# homeboard2.net
KiCad netlist of a schematic drawn in EAGLE
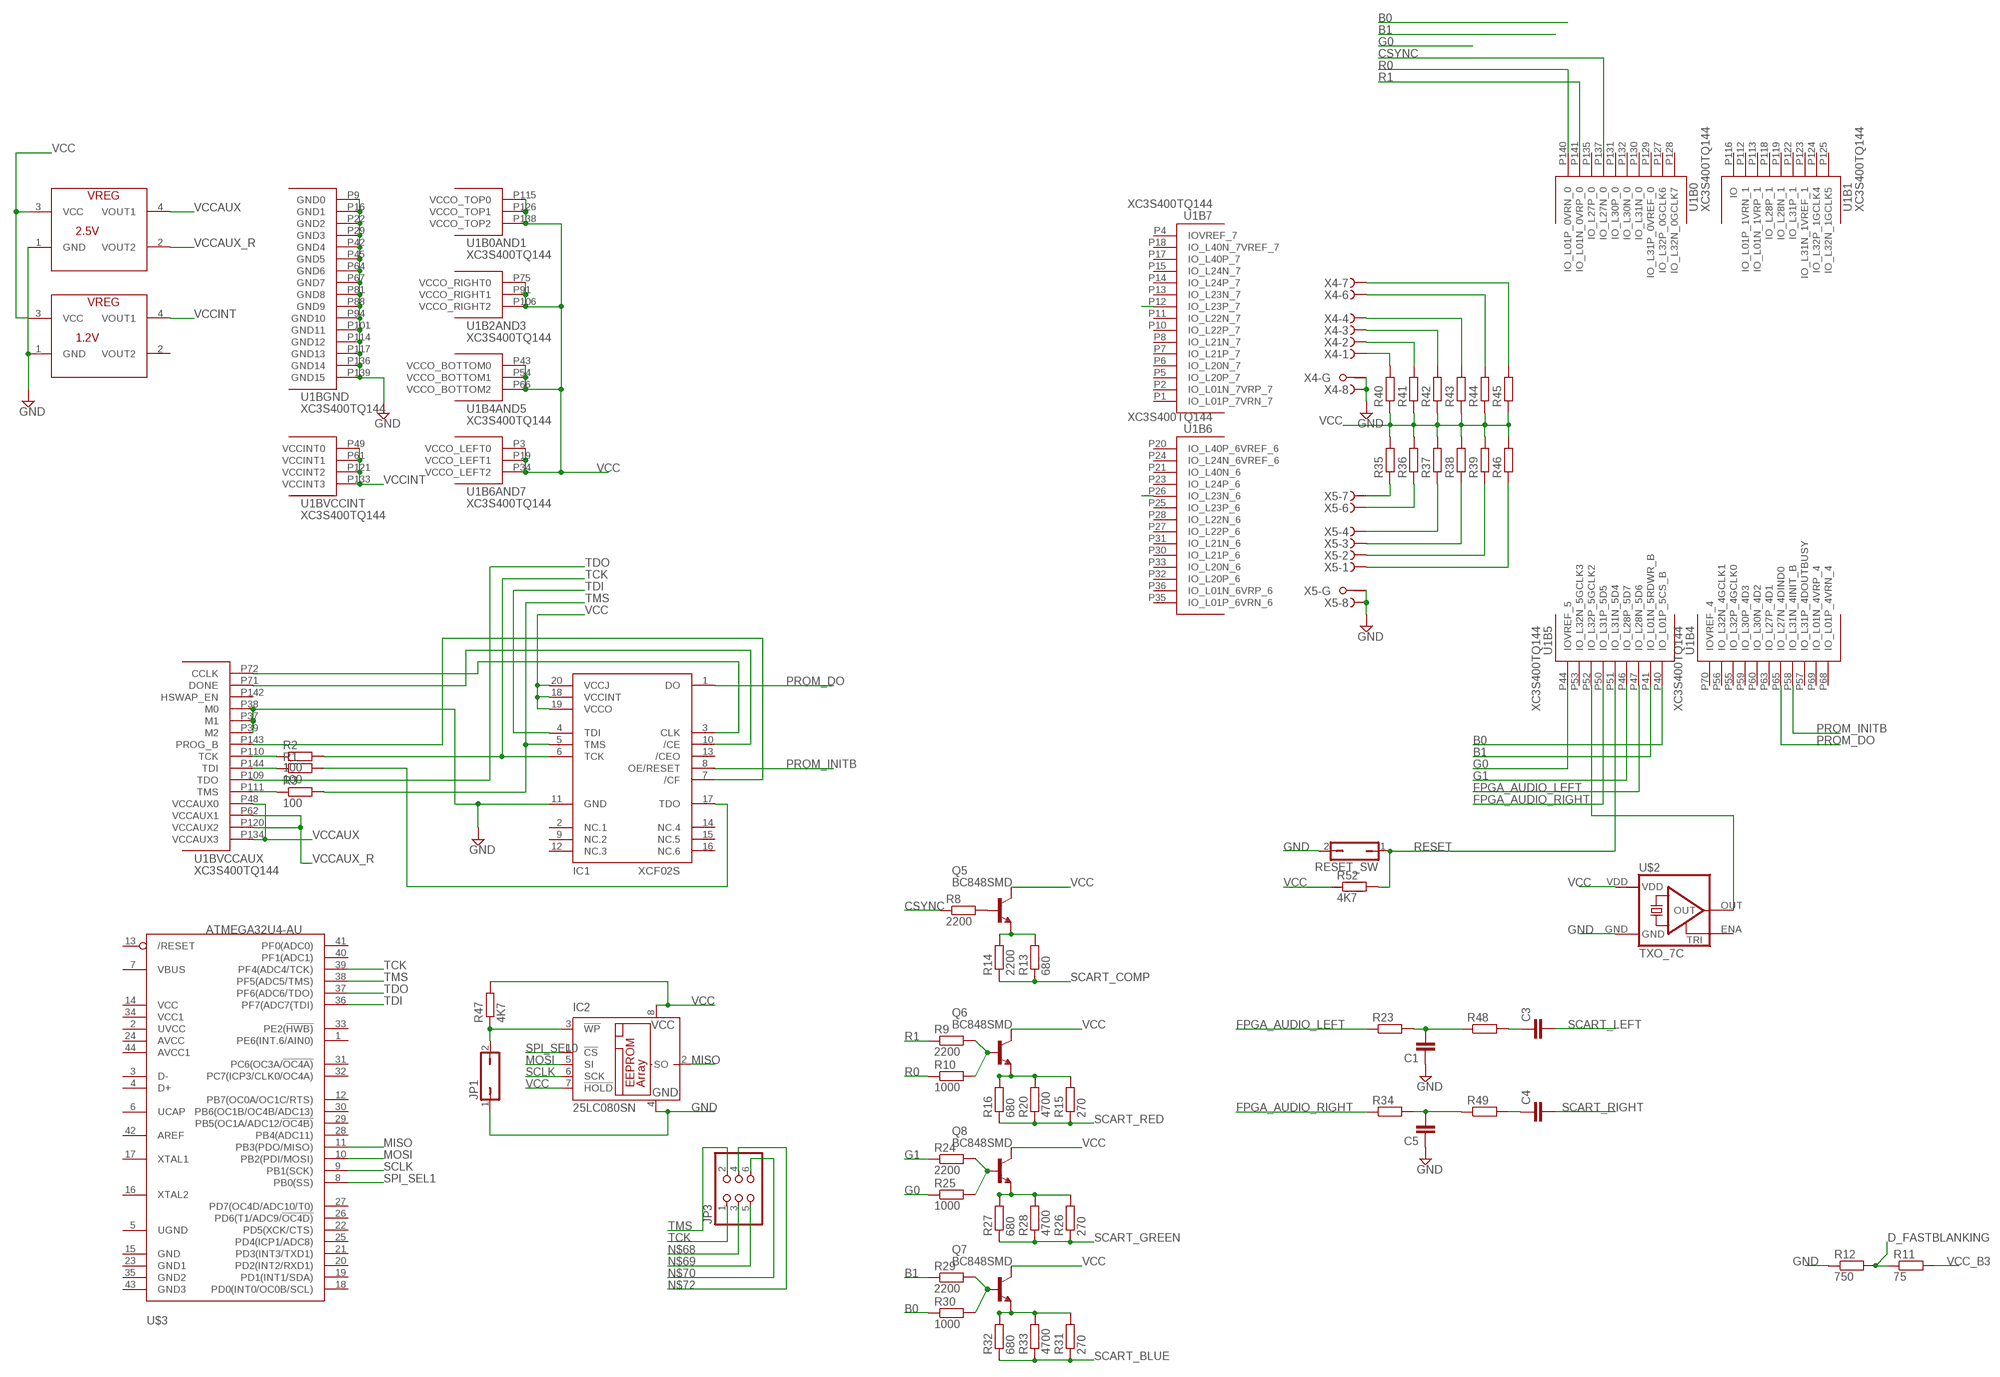
[diagram p0: schematic, sheet 1, part 1 of 3]
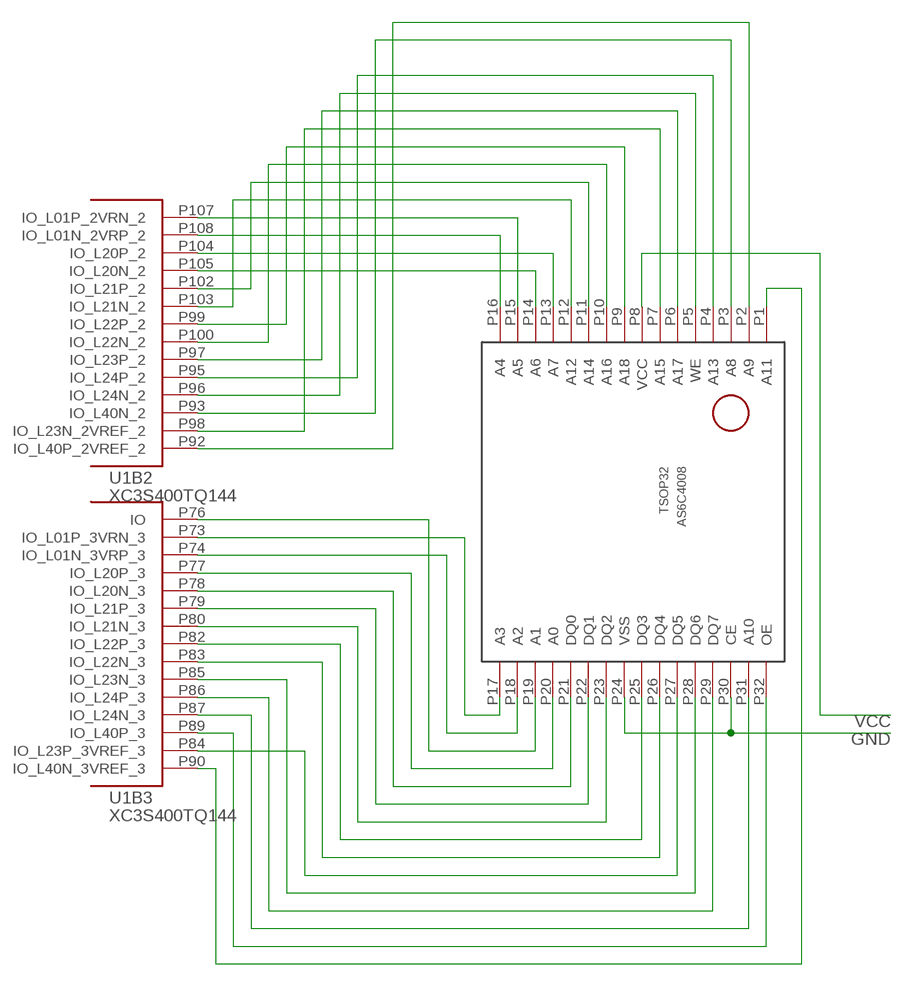
[diagram p1: schematic, sheet 1, part 2 of 3]
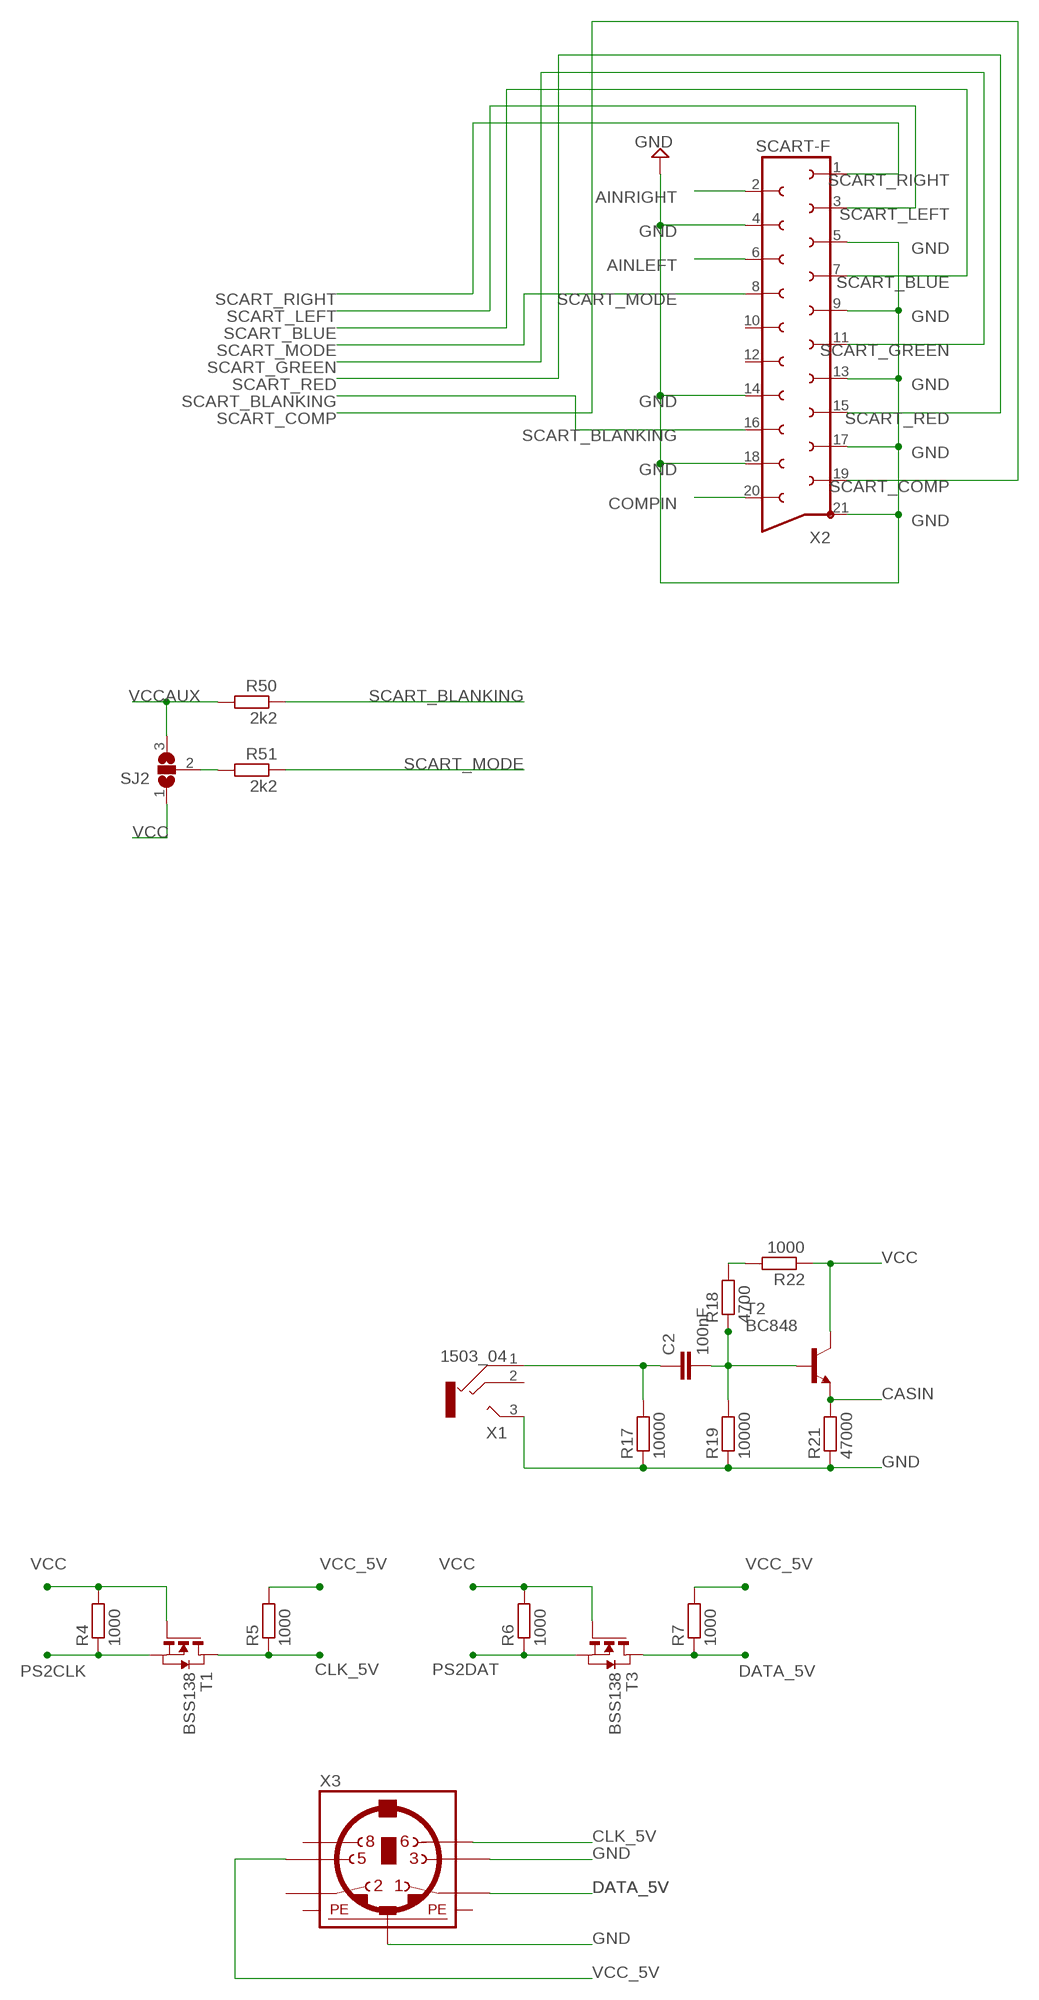
[diagram p2: schematic, sheet 1, part 3 of 3]

(export (version "E")
  (design (tool "Eeschema 10.0.6"))
  (components
    (comp (ref "C1")
      (value "C-EUC0603")
      (footprint "eagle-import:C0603")
      (libsource (lib "eagle-import") (part "C-EUC0603"))
    )
    (comp (ref "C2")
      (value "100nF")
      (footprint "eagle-import:C0603")
      (libsource (lib "eagle-import") (part "C-EUC0603"))
    )
    (comp (ref "C3")
      (value "C-EUC0603")
      (footprint "eagle-import:C0603")
      (libsource (lib "eagle-import") (part "C-EUC0603"))
    )
    (comp (ref "C4")
      (value "C-EUC0603")
      (footprint "eagle-import:C0603")
      (libsource (lib "eagle-import") (part "C-EUC0603"))
    )
    (comp (ref "C5")
      (value "C-EUC0603")
      (footprint "eagle-import:C0603")
      (libsource (lib "eagle-import") (part "C-EUC0603"))
    )
    (comp (ref "IC1")
      (value "XCF02S")
      (footprint "eagle-import:VO20")
      (libsource (lib "eagle-import") (part "XCF02S"))
    )
    (comp (ref "IC2")
      (value "25LC080SN")
      (footprint "eagle-import:SO-08")
      (fields (field (name "MF") "MICROCHIP") (field (name "MPN") "25LC080/SN"))
      (libsource (lib "eagle-import") (part "25SNLC080"))
    )
    (comp (ref "JP1")
      (value "JP1Q")
      (footprint "eagle-import:JP1")
      (libsource (lib "eagle-import") (part "JP1Q"))
    )
    (comp (ref "JP3")
      (value "PINHD-2X3")
      (footprint "eagle-import:2X03")
      (libsource (lib "eagle-import") (part "PINHD-2X3"))
    )
    (comp (ref "Q5")
      (value "BC848SMD")
      (footprint "eagle-import:SOT23")
      (libsource (lib "eagle-import") (part "BC848SMD"))
    )
    (comp (ref "Q6")
      (value "BC848SMD")
      (footprint "eagle-import:SOT23")
      (libsource (lib "eagle-import") (part "BC848SMD"))
    )
    (comp (ref "Q7")
      (value "BC848SMD")
      (footprint "eagle-import:SOT23")
      (libsource (lib "eagle-import") (part "BC848SMD"))
    )
    (comp (ref "Q8")
      (value "BC848SMD")
      (footprint "eagle-import:SOT23")
      (libsource (lib "eagle-import") (part "BC848SMD"))
    )
    (comp (ref "R1")
      (value "100")
      (footprint "eagle-import:R0805")
      (libsource (lib "eagle-import") (part "R-EU_R0805"))
    )
    (comp (ref "R2")
      (value "100")
      (footprint "eagle-import:R0805")
      (libsource (lib "eagle-import") (part "R-EU_R0805"))
    )
    (comp (ref "R3")
      (value "100")
      (footprint "eagle-import:R0805")
      (libsource (lib "eagle-import") (part "R-EU_R0805"))
    )
    (comp (ref "R4")
      (value "1000")
      (footprint "eagle-import:R0805")
      (libsource (lib "eagle-import") (part "R-EU_R0805"))
    )
    (comp (ref "R5")
      (value "1000")
      (footprint "eagle-import:R0805")
      (libsource (lib "eagle-import") (part "R-EU_R0805"))
    )
    (comp (ref "R6")
      (value "1000")
      (footprint "eagle-import:R0805")
      (libsource (lib "eagle-import") (part "R-EU_R0805"))
    )
    (comp (ref "R7")
      (value "1000")
      (footprint "eagle-import:R0805")
      (libsource (lib "eagle-import") (part "R-EU_R0805"))
    )
    (comp (ref "R8")
      (value "2200")
      (footprint "eagle-import:R0805")
      (libsource (lib "eagle-import") (part "R-EU_R0805"))
    )
    (comp (ref "R9")
      (value "2200")
      (footprint "eagle-import:R0805")
      (libsource (lib "eagle-import") (part "R-EU_R0805"))
    )
    (comp (ref "R10")
      (value "1000")
      (footprint "eagle-import:R0805")
      (libsource (lib "eagle-import") (part "R-EU_R0805"))
    )
    (comp (ref "R11")
      (value "75")
      (footprint "eagle-import:R0805")
      (libsource (lib "eagle-import") (part "R-EU_R0805"))
    )
    (comp (ref "R12")
      (value "750")
      (footprint "eagle-import:R0805")
      (libsource (lib "eagle-import") (part "R-EU_R0805"))
    )
    (comp (ref "R13")
      (value "680")
      (footprint "eagle-import:R0805")
      (libsource (lib "eagle-import") (part "R-EU_R0805"))
    )
    (comp (ref "R14")
      (value "2200")
      (footprint "eagle-import:R0805")
      (libsource (lib "eagle-import") (part "R-EU_R0805"))
    )
    (comp (ref "R15")
      (value "270")
      (footprint "eagle-import:R0805")
      (libsource (lib "eagle-import") (part "R-EU_R0805"))
    )
    (comp (ref "R16")
      (value "680")
      (footprint "eagle-import:R0805")
      (libsource (lib "eagle-import") (part "R-EU_R0805"))
    )
    (comp (ref "R17")
      (value "10000")
      (footprint "eagle-import:R0805")
      (libsource (lib "eagle-import") (part "R-EU_R0805"))
    )
    (comp (ref "R18")
      (value "4700")
      (footprint "eagle-import:R0805")
      (libsource (lib "eagle-import") (part "R-EU_R0805"))
    )
    (comp (ref "R19")
      (value "10000")
      (footprint "eagle-import:R0805")
      (libsource (lib "eagle-import") (part "R-EU_R0805"))
    )
    (comp (ref "R20")
      (value "4700")
      (footprint "eagle-import:R0805")
      (libsource (lib "eagle-import") (part "R-EU_R0805"))
    )
    (comp (ref "R21")
      (value "47000")
      (footprint "eagle-import:R0805")
      (libsource (lib "eagle-import") (part "R-EU_R0805"))
    )
    (comp (ref "R22")
      (value "1000")
      (footprint "eagle-import:R0805")
      (libsource (lib "eagle-import") (part "R-EU_R0805"))
    )
    (comp (ref "R23")
      (value "R-EU_M0805")
      (footprint "eagle-import:M0805")
      (libsource (lib "eagle-import") (part "resistor_R-EU_M0805"))
    )
    (comp (ref "R24")
      (value "2200")
      (footprint "eagle-import:R0805")
      (libsource (lib "eagle-import") (part "R-EU_R0805"))
    )
    (comp (ref "R25")
      (value "1000")
      (footprint "eagle-import:R0805")
      (libsource (lib "eagle-import") (part "R-EU_R0805"))
    )
    (comp (ref "R26")
      (value "270")
      (footprint "eagle-import:R0805")
      (libsource (lib "eagle-import") (part "R-EU_R0805"))
    )
    (comp (ref "R27")
      (value "680")
      (footprint "eagle-import:R0805")
      (libsource (lib "eagle-import") (part "R-EU_R0805"))
    )
    (comp (ref "R28")
      (value "4700")
      (footprint "eagle-import:R0805")
      (libsource (lib "eagle-import") (part "R-EU_R0805"))
    )
    (comp (ref "R29")
      (value "2200")
      (footprint "eagle-import:R0805")
      (libsource (lib "eagle-import") (part "R-EU_R0805"))
    )
    (comp (ref "R30")
      (value "1000")
      (footprint "eagle-import:R0805")
      (libsource (lib "eagle-import") (part "R-EU_R0805"))
    )
    (comp (ref "R31")
      (value "270")
      (footprint "eagle-import:R0805")
      (libsource (lib "eagle-import") (part "R-EU_R0805"))
    )
    (comp (ref "R32")
      (value "680")
      (footprint "eagle-import:R0805")
      (libsource (lib "eagle-import") (part "R-EU_R0805"))
    )
    (comp (ref "R33")
      (value "4700")
      (footprint "eagle-import:R0805")
      (libsource (lib "eagle-import") (part "R-EU_R0805"))
    )
    (comp (ref "R34")
      (value "R-EU_M0805")
      (footprint "eagle-import:M0805")
      (libsource (lib "eagle-import") (part "resistor_R-EU_M0805"))
    )
    (comp (ref "R35")
      (value "R-EU_M0805")
      (footprint "eagle-import:M0805")
      (libsource (lib "eagle-import") (part "resistor_R-EU_M0805"))
    )
    (comp (ref "R36")
      (value "R-EU_M0805")
      (footprint "eagle-import:M0805")
      (libsource (lib "eagle-import") (part "resistor_R-EU_M0805"))
    )
    (comp (ref "R37")
      (value "R-EU_M0805")
      (footprint "eagle-import:M0805")
      (libsource (lib "eagle-import") (part "resistor_R-EU_M0805"))
    )
    (comp (ref "R38")
      (value "R-EU_M0805")
      (footprint "eagle-import:M0805")
      (libsource (lib "eagle-import") (part "resistor_R-EU_M0805"))
    )
    (comp (ref "R39")
      (value "R-EU_M0805")
      (footprint "eagle-import:M0805")
      (libsource (lib "eagle-import") (part "resistor_R-EU_M0805"))
    )
    (comp (ref "R40")
      (value "R-EU_M0805")
      (footprint "eagle-import:M0805")
      (libsource (lib "eagle-import") (part "resistor_R-EU_M0805"))
    )
    (comp (ref "R41")
      (value "R-EU_M0805")
      (footprint "eagle-import:M0805")
      (libsource (lib "eagle-import") (part "resistor_R-EU_M0805"))
    )
    (comp (ref "R42")
      (value "R-EU_M0805")
      (footprint "eagle-import:M0805")
      (libsource (lib "eagle-import") (part "resistor_R-EU_M0805"))
    )
    (comp (ref "R43")
      (value "R-EU_M0805")
      (footprint "eagle-import:M0805")
      (libsource (lib "eagle-import") (part "resistor_R-EU_M0805"))
    )
    (comp (ref "R44")
      (value "R-EU_M0805")
      (footprint "eagle-import:M0805")
      (libsource (lib "eagle-import") (part "resistor_R-EU_M0805"))
    )
    (comp (ref "R45")
      (value "R-EU_M0805")
      (footprint "eagle-import:M0805")
      (libsource (lib "eagle-import") (part "resistor_R-EU_M0805"))
    )
    (comp (ref "R46")
      (value "R-EU_M0805")
      (footprint "eagle-import:M0805")
      (libsource (lib "eagle-import") (part "resistor_R-EU_M0805"))
    )
    (comp (ref "R47")
      (value "4K7")
      (footprint "eagle-import:R0805")
      (libsource (lib "eagle-import") (part "R-EU_R0805"))
    )
    (comp (ref "R48")
      (value "R-EU_M0805")
      (footprint "eagle-import:M0805")
      (libsource (lib "eagle-import") (part "resistor_R-EU_M0805"))
    )
    (comp (ref "R49")
      (value "R-EU_M0805")
      (footprint "eagle-import:M0805")
      (libsource (lib "eagle-import") (part "resistor_R-EU_M0805"))
    )
    (comp (ref "R50")
      (value "2k2")
      (footprint "eagle-import:M0805")
      (libsource (lib "eagle-import") (part "resistor_R-EU_M0805"))
    )
    (comp (ref "R51")
      (value "2k2")
      (footprint "eagle-import:M0805")
      (libsource (lib "eagle-import") (part "resistor_R-EU_M0805"))
    )
    (comp (ref "R52")
      (value "4K7")
      (footprint "eagle-import:M0805")
      (libsource (lib "eagle-import") (part "resistor_R-EU_M0805"))
    )
    (comp (ref "REG1.2")
      (value "1.2V")
      (footprint "eagle-import:SOT223")
      (libsource (lib "eagle-import") (part "NX1117"))
    )
    (comp (ref "REG2.5")
      (value "2.5V")
      (footprint "eagle-import:SOT223")
      (libsource (lib "eagle-import") (part "NX1117"))
    )
    (comp (ref "RESET_SW")
      (value "JP1Q")
      (footprint "eagle-import:JP1")
      (libsource (lib "eagle-import") (part "JP1Q"))
    )
    (comp (ref "SJ2")
      (value "SJ2W")
      (footprint "eagle-import:SJ_2")
      (libsource (lib "eagle-import") (part "SJ2W"))
    )
    (comp (ref "T1")
      (value "BSS138")
      (footprint "eagle-import:SOT-23")
      (libsource (lib "eagle-import") (part "NMOSSOT23"))
    )
    (comp (ref "T2")
      (value "BC848")
      (footprint "eagle-import:SOT23")
      (libsource (lib "eagle-import") (part "BC848"))
    )
    (comp (ref "T3")
      (value "BSS138")
      (footprint "eagle-import:SOT-23")
      (libsource (lib "eagle-import") (part "NMOSSOT23"))
    )
    (comp (ref "U$1")
      (value "AS6C4008")
      (footprint "eagle-import:TSOP32")
      (libsource (lib "eagle-import") (part "AS6C4008"))
    )
    (comp (ref "U$2")
      (value "TXO_7C")
      (footprint "eagle-import:OSC_7C")
      (libsource (lib "eagle-import") (part "TXO_7C"))
    )
    (comp (ref "U$3")
      (value "ATMEGA32U4-AU")
      (footprint "eagle-import:TQFP44")
      (libsource (lib "eagle-import") (part "ATMEGA32U4-AU"))
    )
    (comp (ref "U1")
      (value "XC3S400TQ144")
      (footprint "eagle-import:TQ144")
      (libsource (lib "eagle-import") (part "XC3S400TQ144"))
    )
    (comp (ref "X1")
      (value "1503_04")
      (footprint "eagle-import:1503_04")
      (libsource (lib "eagle-import") (part "1503_04"))
    )
    (comp (ref "X2")
      (value "SCART-F")
      (footprint "eagle-import:SCART-F")
      (libsource (lib "eagle-import") (part "SCART-F"))
    )
    (comp (ref "X3")
      (value "MINI_DIN_6")
      (footprint "eagle-import:M_DIN6")
      (libsource (lib "eagle-import") (part "MINI_DIN_6"))
    )
    (comp (ref "X4")
      (value "F09HPS")
      (footprint "eagle-import:F09HP")
      (libsource (lib "eagle-import") (part "F09HPS"))
    )
    (comp (ref "X5")
      (value "F09HPS")
      (footprint "eagle-import:F09HP")
      (libsource (lib "eagle-import") (part "F09HPS"))
    )
  )
  (nets
    (net (code "1") (name "/AINLEFT") (class "Default")
      (node (ref "X2") (pin "6") (pinfunction "6_6") (pintype "passive"))
    )
    (net (code "2") (name "/AINRIGHT") (class "Default")
      (node (ref "X2") (pin "2") (pinfunction "2_2") (pintype "passive"))
    )
    (net (code "3") (name "/B0") (class "Default")
      (node (ref "R30") (pin "1") (pinfunction "1_1") (pintype "passive"))
      (node (ref "U1") (pin "P40") (pinfunction "IO_L01P_5CS_B_P40") (pintype "bidirectional"))
    )
    (net (code "4") (name "/B1") (class "Default")
      (node (ref "R29") (pin "1") (pinfunction "1_1") (pintype "passive"))
      (node (ref "U1") (pin "P41") (pinfunction "IO_L01N_5RDWR_B_P41") (pintype "bidirectional"))
    )
    (net (code "5") (name "/CASIN") (class "Default")
      (node (ref "R21") (pin "2") (pinfunction "2_2") (pintype "passive"))
      (node (ref "T2") (pin "2") (pinfunction "E_2") (pintype "passive"))
    )
    (net (code "6") (name "/CLK_5V") (class "Default")
      (node (ref "R5") (pin "1") (pinfunction "1_1") (pintype "passive"))
      (node (ref "T1") (pin "1") (pinfunction "D_1") (pintype "passive"))
      (node (ref "X3") (pin "6") (pinfunction "6_6") (pintype "passive"))
    )
    (net (code "7") (name "/COMPIN") (class "Default")
      (node (ref "X2") (pin "20") (pinfunction "20_20") (pintype "passive"))
    )
    (net (code "8") (name "/CSYNC") (class "Default")
      (node (ref "R8") (pin "1") (pinfunction "1_1") (pintype "passive"))
      (node (ref "U1") (pin "P137") (pinfunction "IO_L27N_0_P137") (pintype "bidirectional"))
    )
    (net (code "9") (name "/DATA_5V") (class "Default")
      (node (ref "R7") (pin "1") (pinfunction "1_1") (pintype "passive"))
      (node (ref "T3") (pin "1") (pinfunction "D_1") (pintype "passive"))
      (node (ref "X3") (pin "1") (pinfunction "1_1") (pintype "passive"))
    )
    (net (code "10") (name "/D_FASTBLANKING") (class "Default")
      (node (ref "R11") (pin "1") (pinfunction "1_1") (pintype "passive"))
      (node (ref "R12") (pin "2") (pinfunction "2_2") (pintype "passive"))
    )
    (net (code "11") (name "/FPGA_AUDIO_LEFT") (class "Default")
      (node (ref "R23") (pin "1") (pinfunction "1_1") (pintype "passive"))
      (node (ref "U1") (pin "P47") (pinfunction "IO_L28N_5D6_P47") (pintype "bidirectional"))
    )
    (net (code "12") (name "/FPGA_AUDIO_RIGHT") (class "Default")
      (node (ref "R34") (pin "1") (pinfunction "1_1") (pintype "passive"))
      (node (ref "U1") (pin "P50") (pinfunction "IO_L31P_5D5_P50") (pintype "bidirectional"))
    )
    (net (code "13") (name "/G0") (class "Default")
      (node (ref "R25") (pin "1") (pinfunction "1_1") (pintype "passive"))
      (node (ref "U1") (pin "P44") (pinfunction "IOVREF_5_P44") (pintype "bidirectional"))
    )
    (net (code "14") (name "/G1") (class "Default")
      (node (ref "R24") (pin "1") (pinfunction "1_1") (pintype "passive"))
      (node (ref "U1") (pin "P46") (pinfunction "IO_L28P_5D7_P46") (pintype "bidirectional"))
    )
    (net (code "15") (name "/MISO") (class "Default")
      (node (ref "IC2") (pin "2") (pinfunction "SO_2") (pintype "bidirectional"))
      (node (ref "U$3") (pin "11") (pinfunction "PB3(PDO/MISO)_11") (pintype "bidirectional"))
    )
    (net (code "16") (name "/MOSI") (class "Default")
      (node (ref "IC2") (pin "5") (pinfunction "SI_5") (pintype "input"))
      (node (ref "U$3") (pin "10") (pinfunction "PB2(PDI/MOSI)_10") (pintype "bidirectional"))
    )
    (net (code "17") (name "/N$68") (class "Default")
      (node (ref "JP3") (pin "3") (pinfunction "3_3") (pintype "passive"))
    )
    (net (code "18") (name "/N$69") (class "Default")
      (node (ref "JP3") (pin "5") (pinfunction "5_5") (pintype "passive"))
    )
    (net (code "19") (name "/N$70") (class "Default")
      (node (ref "JP3") (pin "6") (pinfunction "6_6") (pintype "passive"))
    )
    (net (code "20") (name "/N$72") (class "Default")
      (node (ref "JP3") (pin "4") (pinfunction "4_4") (pintype "passive"))
    )
    (net (code "21") (name "/PE1") (class "Default")
      (node (ref "X3") (pin "SH1") (pinfunction "PE1_SH1") (pintype "power_in"))
    )
    (net (code "22") (name "/PE3") (class "Default")
      (node (ref "X3") (pin "SH3") (pinfunction "PE3_SH3") (pintype "power_in"))
    )
    (net (code "23") (name "/PROM_DO") (class "Default")
      (node (ref "IC1") (pin "1") (pinfunction "DO_1") (pintype "bidirectional"))
      (node (ref "U1") (pin "P65") (pinfunction "IO_L27N_4DIND0_P65") (pintype "bidirectional"))
    )
    (net (code "24") (name "/PROM_INITB") (class "Default")
      (node (ref "IC1") (pin "8") (pinfunction "OE/RESET_8") (pintype "bidirectional"))
      (node (ref "U1") (pin "P58") (pinfunction "IO_L31N_4INIT_B_P58") (pintype "bidirectional"))
    )
    (net (code "25") (name "/PS2CLK") (class "Default")
      (node (ref "R4") (pin "1") (pinfunction "1_1") (pintype "passive"))
      (node (ref "T1") (pin "2") (pinfunction "S_2") (pintype "passive"))
    )
    (net (code "26") (name "/PS2DAT") (class "Default")
      (node (ref "R6") (pin "1") (pinfunction "1_1") (pintype "passive"))
      (node (ref "T3") (pin "2") (pinfunction "S_2") (pintype "passive"))
    )
    (net (code "27") (name "/R0") (class "Default")
      (node (ref "R10") (pin "1") (pinfunction "1_1") (pintype "passive"))
      (node (ref "U1") (pin "P140") (pinfunction "IO_L01P_0VRN_0_P140") (pintype "bidirectional"))
    )
    (net (code "28") (name "/R1") (class "Default")
      (node (ref "R9") (pin "1") (pinfunction "1_1") (pintype "passive"))
      (node (ref "U1") (pin "P141") (pinfunction "IO_L01N_0VRP_0_P141") (pintype "bidirectional"))
    )
    (net (code "29") (name "/RESET") (class "Default")
      (node (ref "R52") (pin "2") (pinfunction "2_2") (pintype "passive"))
      (node (ref "RESET_SW") (pin "1") (pinfunction "1_1") (pintype "passive"))
      (node (ref "U1") (pin "P51") (pinfunction "IO_L31N_5D4_P51") (pintype "bidirectional"))
    )
    (net (code "30") (name "/SCART_BLANKING") (class "Default")
      (node (ref "R50") (pin "1") (pinfunction "1_1") (pintype "passive"))
      (node (ref "X2") (pin "16") (pinfunction "16_16") (pintype "passive"))
    )
    (net (code "31") (name "/SCART_BLUE") (class "Default")
      (node (ref "R31") (pin "1") (pinfunction "1_1") (pintype "passive"))
      (node (ref "R32") (pin "1") (pinfunction "1_1") (pintype "passive"))
      (node (ref "R33") (pin "1") (pinfunction "1_1") (pintype "passive"))
      (node (ref "X2") (pin "7") (pinfunction "7_7") (pintype "passive"))
    )
    (net (code "32") (name "/SCART_COMP") (class "Default")
      (node (ref "R13") (pin "1") (pinfunction "1_1") (pintype "passive"))
      (node (ref "R14") (pin "1") (pinfunction "1_1") (pintype "passive"))
      (node (ref "X2") (pin "19") (pinfunction "19_19") (pintype "passive"))
    )
    (net (code "33") (name "/SCART_GREEN") (class "Default")
      (node (ref "R26") (pin "1") (pinfunction "1_1") (pintype "passive"))
      (node (ref "R27") (pin "1") (pinfunction "1_1") (pintype "passive"))
      (node (ref "R28") (pin "1") (pinfunction "1_1") (pintype "passive"))
      (node (ref "X2") (pin "11") (pinfunction "11_11") (pintype "passive"))
    )
    (net (code "34") (name "/SCART_LEFT") (class "Default")
      (node (ref "C3") (pin "2") (pinfunction "2_2") (pintype "passive"))
      (node (ref "X2") (pin "3") (pinfunction "3_3") (pintype "passive"))
    )
    (net (code "35") (name "/SCART_MODE") (class "Default")
      (node (ref "R51") (pin "1") (pinfunction "1_1") (pintype "passive"))
      (node (ref "X2") (pin "8") (pinfunction "8_8") (pintype "passive"))
    )
    (net (code "36") (name "/SCART_RED") (class "Default")
      (node (ref "R15") (pin "1") (pinfunction "1_1") (pintype "passive"))
      (node (ref "R16") (pin "1") (pinfunction "1_1") (pintype "passive"))
      (node (ref "R20") (pin "1") (pinfunction "1_1") (pintype "passive"))
      (node (ref "X2") (pin "15") (pinfunction "15_15") (pintype "passive"))
    )
    (net (code "37") (name "/SCART_RIGHT") (class "Default")
      (node (ref "C4") (pin "2") (pinfunction "2_2") (pintype "passive"))
      (node (ref "X2") (pin "1") (pinfunction "1_1") (pintype "passive"))
    )
    (net (code "38") (name "/SCLK") (class "Default")
      (node (ref "IC2") (pin "6") (pinfunction "SCK_6") (pintype "input"))
      (node (ref "U$3") (pin "9") (pinfunction "PB1(SCK)_9") (pintype "bidirectional"))
    )
    (net (code "39") (name "/SPI_SEL0") (class "Default")
      (node (ref "IC2") (pin "1") (pinfunction "~{CS}_1") (pintype "input"))
    )
    (net (code "40") (name "/SPI_SEL1") (class "Default")
      (node (ref "U$3") (pin "8") (pinfunction "PB0(SS)_8") (pintype "bidirectional"))
    )
    (net (code "41") (name "/TCK") (class "Default")
      (node (ref "IC1") (pin "6") (pinfunction "TCK_6") (pintype "bidirectional"))
      (node (ref "JP3") (pin "1") (pinfunction "1_1") (pintype "passive"))
      (node (ref "R2") (pin "2") (pinfunction "2_2") (pintype "passive"))
      (node (ref "U$3") (pin "39") (pinfunction "PF4(ADC4/TCK)_39") (pintype "bidirectional"))
    )
    (net (code "42") (name "/TDI") (class "Default")
      (node (ref "IC1") (pin "4") (pinfunction "TDI_4") (pintype "bidirectional"))
      (node (ref "U$3") (pin "36") (pinfunction "PF7(ADC7(TDI)_36") (pintype "bidirectional"))
    )
    (net (code "43") (name "/TDO") (class "Default")
      (node (ref "U$3") (pin "37") (pinfunction "PF6(ADC6/TDO)_37") (pintype "bidirectional"))
      (node (ref "U1") (pin "P109") (pinfunction "TDO_P109") (pintype "bidirectional"))
    )
    (net (code "44") (name "/TMS") (class "Default")
      (node (ref "IC1") (pin "5") (pinfunction "TMS_5") (pintype "bidirectional"))
      (node (ref "JP3") (pin "2") (pinfunction "2_2") (pintype "passive"))
      (node (ref "R3") (pin "2") (pinfunction "2_2") (pintype "passive"))
      (node (ref "U$3") (pin "38") (pinfunction "PF5(ADC5/TMS)_38") (pintype "bidirectional"))
    )
    (net (code "45") (name "/VCC") (class "Default")
      (node (ref "IC1") (pin "18") (pinfunction "VCCINT_18") (pintype "bidirectional"))
      (node (ref "IC1") (pin "19") (pinfunction "VCCO_19") (pintype "bidirectional"))
      (node (ref "IC1") (pin "20") (pinfunction "VCCJ_20") (pintype "bidirectional"))
      (node (ref "IC2") (pin "7") (pinfunction "~{HOLD}_7") (pintype "input"))
      (node (ref "IC2") (pin "8") (pinfunction "VCC_8") (pintype "power_in"))
      (node (ref "Q5") (pin "3") (pinfunction "C_3") (pintype "passive"))
      (node (ref "Q6") (pin "3") (pinfunction "C_3") (pintype "passive"))
      (node (ref "Q7") (pin "3") (pinfunction "C_3") (pintype "passive"))
      (node (ref "Q8") (pin "3") (pinfunction "C_3") (pintype "passive"))
      (node (ref "R22") (pin "1") (pinfunction "1_1") (pintype "passive"))
      (node (ref "R35") (pin "2") (pinfunction "2_2") (pintype "passive"))
      (node (ref "R36") (pin "2") (pinfunction "2_2") (pintype "passive"))
      (node (ref "R37") (pin "2") (pinfunction "2_2") (pintype "passive"))
      (node (ref "R38") (pin "2") (pinfunction "2_2") (pintype "passive"))
      (node (ref "R39") (pin "2") (pinfunction "2_2") (pintype "passive"))
      (node (ref "R4") (pin "2") (pinfunction "2_2") (pintype "passive"))
      (node (ref "R40") (pin "1") (pinfunction "1_1") (pintype "passive"))
      (node (ref "R41") (pin "1") (pinfunction "1_1") (pintype "passive"))
      (node (ref "R42") (pin "1") (pinfunction "1_1") (pintype "passive"))
      (node (ref "R43") (pin "1") (pinfunction "1_1") (pintype "passive"))
      (node (ref "R44") (pin "1") (pinfunction "1_1") (pintype "passive"))
      (node (ref "R45") (pin "1") (pinfunction "1_1") (pintype "passive"))
      (node (ref "R46") (pin "2") (pinfunction "2_2") (pintype "passive"))
      (node (ref "R47") (pin "2") (pinfunction "2_2") (pintype "passive"))
      (node (ref "R52") (pin "1") (pinfunction "1_1") (pintype "passive"))
      (node (ref "R6") (pin "2") (pinfunction "2_2") (pintype "passive"))
      (node (ref "REG1.2") (pin "3") (pinfunction "VCC_3") (pintype "bidirectional"))
      (node (ref "REG2.5") (pin "3") (pinfunction "VCC_3") (pintype "bidirectional"))
      (node (ref "SJ2") (pin "1") (pinfunction "1_1") (pintype "passive"))
      (node (ref "T1") (pin "3") (pinfunction "G_3") (pintype "passive"))
      (node (ref "T2") (pin "3") (pinfunction "C_3") (pintype "passive"))
      (node (ref "T3") (pin "3") (pinfunction "G_3") (pintype "passive"))
      (node (ref "U$1") (pin "P8") (pinfunction "VCC_P8") (pintype "bidirectional"))
      (node (ref "U$2") (pin "VDD") (pinfunction "VDD_VDD") (pintype "power_in"))
      (node (ref "U1") (pin "P106") (pinfunction "VCCO_RIGHT2_P106") (pintype "passive"))
      (node (ref "U1") (pin "P115") (pinfunction "VCCO_TOP0_P115") (pintype "passive"))
      (node (ref "U1") (pin "P126") (pinfunction "VCCO_TOP1_P126") (pintype "passive"))
      (node (ref "U1") (pin "P138") (pinfunction "VCCO_TOP2_P138") (pintype "passive"))
      (node (ref "U1") (pin "P19") (pinfunction "VCCO_LEFT1_P19") (pintype "passive"))
      (node (ref "U1") (pin "P3") (pinfunction "VCCO_LEFT0_P3") (pintype "passive"))
      (node (ref "U1") (pin "P34") (pinfunction "VCCO_LEFT2_P34") (pintype "passive"))
      (node (ref "U1") (pin "P43") (pinfunction "VCCO_BOTTOM0_P43") (pintype "passive"))
      (node (ref "U1") (pin "P54") (pinfunction "VCCO_BOTTOM1_P54") (pintype "passive"))
      (node (ref "U1") (pin "P66") (pinfunction "VCCO_BOTTOM2_P66") (pintype "passive"))
      (node (ref "U1") (pin "P75") (pinfunction "VCCO_RIGHT0_P75") (pintype "passive"))
      (node (ref "U1") (pin "P91") (pinfunction "VCCO_RIGHT1_P91") (pintype "passive"))
    )
    (net (code "46") (name "/VCCAUX") (class "Default")
      (node (ref "R50") (pin "2") (pinfunction "2_2") (pintype "passive"))
      (node (ref "REG2.5") (pin "4") (pinfunction "VOUT1_4") (pintype "bidirectional"))
      (node (ref "SJ2") (pin "3") (pinfunction "3_3") (pintype "passive"))
      (node (ref "U1") (pin "P134") (pinfunction "VCCAUX3_P134") (pintype "passive"))
      (node (ref "U1") (pin "P48") (pinfunction "VCCAUX0_P48") (pintype "passive"))
    )
    (net (code "47") (name "/VCCAUX_R") (class "Default")
      (node (ref "REG2.5") (pin "2") (pinfunction "VOUT2_2") (pintype "bidirectional"))
      (node (ref "U1") (pin "P120") (pinfunction "VCCAUX2_P120") (pintype "passive"))
      (node (ref "U1") (pin "P62") (pinfunction "VCCAUX1_P62") (pintype "passive"))
    )
    (net (code "48") (name "/VCCINT") (class "Default")
      (node (ref "REG1.2") (pin "4") (pinfunction "VOUT1_4") (pintype "bidirectional"))
      (node (ref "U1") (pin "P121") (pinfunction "VCCINT2_P121") (pintype "passive"))
      (node (ref "U1") (pin "P133") (pinfunction "VCCINT3_P133") (pintype "passive"))
      (node (ref "U1") (pin "P49") (pinfunction "VCCINT0_P49") (pintype "passive"))
      (node (ref "U1") (pin "P61") (pinfunction "VCCINT1_P61") (pintype "passive"))
    )
    (net (code "49") (name "/VCC_5V") (class "Default")
      (node (ref "R5") (pin "2") (pinfunction "2_2") (pintype "passive"))
      (node (ref "R7") (pin "2") (pinfunction "2_2") (pintype "passive"))
      (node (ref "X3") (pin "5") (pinfunction "5_5") (pintype "passive"))
    )
    (net (code "50") (name "/VCC_B3") (class "Default")
      (node (ref "R11") (pin "2") (pinfunction "2_2") (pintype "passive"))
    )
    (net (code "51") (name "GND") (class "Default")
      (node (ref "C1") (pin "1") (pinfunction "1_1") (pintype "passive"))
      (node (ref "C5") (pin "1") (pinfunction "1_1") (pintype "passive"))
      (node (ref "IC1") (pin "11") (pinfunction "GND_11") (pintype "bidirectional"))
      (node (ref "IC2") (pin "4") (pinfunction "GND_4") (pintype "power_in"))
      (node (ref "JP1") (pin "1") (pinfunction "1_1") (pintype "passive"))
      (node (ref "R12") (pin "1") (pinfunction "1_1") (pintype "passive"))
      (node (ref "R17") (pin "1") (pinfunction "1_1") (pintype "passive"))
      (node (ref "R19") (pin "1") (pinfunction "1_1") (pintype "passive"))
      (node (ref "R21") (pin "1") (pinfunction "1_1") (pintype "passive"))
      (node (ref "REG1.2") (pin "1") (pinfunction "GND_1") (pintype "bidirectional"))
      (node (ref "REG2.5") (pin "1") (pinfunction "GND_1") (pintype "bidirectional"))
      (node (ref "RESET_SW") (pin "2") (pinfunction "2_2") (pintype "passive"))
      (node (ref "U$1") (pin "P24") (pinfunction "VSS_P24") (pintype "bidirectional"))
      (node (ref "U$1") (pin "P30") (pinfunction "CE_P30") (pintype "bidirectional"))
      (node (ref "U$2") (pin "GND") (pinfunction "GND_GND") (pintype "power_in"))
      (node (ref "U1") (pin "P101") (pinfunction "GND11_P101") (pintype "passive"))
      (node (ref "U1") (pin "P114") (pinfunction "GND12_P114") (pintype "passive"))
      (node (ref "U1") (pin "P117") (pinfunction "GND13_P117") (pintype "passive"))
      (node (ref "U1") (pin "P136") (pinfunction "GND14_P136") (pintype "passive"))
      (node (ref "U1") (pin "P139") (pinfunction "GND15_P139") (pintype "passive"))
      (node (ref "U1") (pin "P16") (pinfunction "GND1_P16") (pintype "passive"))
      (node (ref "U1") (pin "P22") (pinfunction "GND2_P22") (pintype "passive"))
      (node (ref "U1") (pin "P29") (pinfunction "GND3_P29") (pintype "passive"))
      (node (ref "U1") (pin "P37") (pinfunction "M1_P37") (pintype "bidirectional"))
      (node (ref "U1") (pin "P38") (pinfunction "M0_P38") (pintype "bidirectional"))
      (node (ref "U1") (pin "P39") (pinfunction "M2_P39") (pintype "bidirectional"))
      (node (ref "U1") (pin "P42") (pinfunction "GND4_P42") (pintype "passive"))
      (node (ref "U1") (pin "P45") (pinfunction "GND5_P45") (pintype "passive"))
      (node (ref "U1") (pin "P64") (pinfunction "GND6_P64") (pintype "passive"))
      (node (ref "U1") (pin "P67") (pinfunction "GND7_P67") (pintype "passive"))
      (node (ref "U1") (pin "P81") (pinfunction "GND8_P81") (pintype "passive"))
      (node (ref "U1") (pin "P88") (pinfunction "GND9_P88") (pintype "passive"))
      (node (ref "U1") (pin "P9") (pinfunction "GND0_P9") (pintype "passive"))
      (node (ref "U1") (pin "P94") (pinfunction "GND10_P94") (pintype "passive"))
      (node (ref "X1") (pin "3") (pinfunction "2_3") (pintype "passive"))
      (node (ref "X2") (pin "13") (pinfunction "13_13") (pintype "passive"))
      (node (ref "X2") (pin "14") (pinfunction "14_14") (pintype "passive"))
      (node (ref "X2") (pin "17") (pinfunction "17_17") (pintype "passive"))
      (node (ref "X2") (pin "18") (pinfunction "18_18") (pintype "passive"))
      (node (ref "X2") (pin "21") (pinfunction "21_21") (pintype "passive"))
      (node (ref "X2") (pin "4") (pinfunction "4_4") (pintype "passive"))
      (node (ref "X2") (pin "5") (pinfunction "5_5") (pintype "passive"))
      (node (ref "X2") (pin "9") (pinfunction "9_9") (pintype "passive"))
      (node (ref "X3") (pin "3") (pinfunction "3_3") (pintype "passive"))
      (node (ref "X3") (pin "SH2") (pinfunction "PE2_SH2") (pintype "power_in"))
      (node (ref "X4") (pin "8") (pinfunction "F_8") (pintype "passive"))
      (node (ref "X4") (pin "G1") (pinfunction "G1_G1") (pintype "passive"))
      (node (ref "X5") (pin "8") (pinfunction "F_8") (pintype "passive"))
      (node (ref "X5") (pin "G1") (pinfunction "G1_G1") (pintype "passive"))
    )
    (net (code "52") (name "Net-(C1-Pad2)") (class "Default")
      (node (ref "C1") (pin "2") (pinfunction "2_2") (pintype "passive"))
      (node (ref "R23") (pin "2") (pinfunction "2_2") (pintype "passive"))
      (node (ref "R48") (pin "1") (pinfunction "1_1") (pintype "passive"))
    )
    (net (code "53") (name "Net-(C2-Pad1)") (class "Default")
      (node (ref "C2") (pin "1") (pinfunction "1_1") (pintype "passive"))
      (node (ref "R17") (pin "2") (pinfunction "2_2") (pintype "passive"))
      (node (ref "X1") (pin "1") (pinfunction "1_1") (pintype "passive"))
    )
    (net (code "54") (name "Net-(C3-Pad1)") (class "Default")
      (node (ref "C3") (pin "1") (pinfunction "1_1") (pintype "passive"))
      (node (ref "R48") (pin "2") (pinfunction "2_2") (pintype "passive"))
    )
    (net (code "55") (name "Net-(C4-Pad1)") (class "Default")
      (node (ref "C4") (pin "1") (pinfunction "1_1") (pintype "passive"))
      (node (ref "R49") (pin "2") (pinfunction "2_2") (pintype "passive"))
    )
    (net (code "56") (name "Net-(C5-Pad2)") (class "Default")
      (node (ref "C5") (pin "2") (pinfunction "2_2") (pintype "passive"))
      (node (ref "R34") (pin "2") (pinfunction "2_2") (pintype "passive"))
      (node (ref "R49") (pin "1") (pinfunction "1_1") (pintype "passive"))
    )
    (net (code "57") (name "Net-(IC1-CLK)") (class "Default")
      (node (ref "IC1") (pin "3") (pinfunction "CLK_3") (pintype "bidirectional"))
      (node (ref "U1") (pin "P72") (pinfunction "CCLK_P72") (pintype "bidirectional"))
    )
    (net (code "58") (name "Net-(IC1-TDO)") (class "Default")
      (node (ref "IC1") (pin "17") (pinfunction "TDO_17") (pintype "bidirectional"))
      (node (ref "R1") (pin "2") (pinfunction "2_2") (pintype "passive"))
    )
    (net (code "59") (name "Net-(IC1-{slash}CE)") (class "Default")
      (node (ref "IC1") (pin "10") (pinfunction "/CE_10") (pintype "bidirectional"))
      (node (ref "U1") (pin "P71") (pinfunction "DONE_P71") (pintype "bidirectional"))
    )
    (net (code "60") (name "Net-(IC1-{slash}CF)") (class "Default")
      (node (ref "IC1") (pin "7") (pinfunction "/CF_7") (pintype "bidirectional"))
      (node (ref "U1") (pin "P143") (pinfunction "PROG_B_P143") (pintype "bidirectional"))
    )
    (net (code "61") (name "Net-(IC2-~{WP})") (class "Default")
      (node (ref "IC2") (pin "3") (pinfunction "~{WP}_3") (pintype "input"))
      (node (ref "JP1") (pin "2") (pinfunction "2_2") (pintype "passive"))
      (node (ref "R47") (pin "1") (pinfunction "1_1") (pintype "passive"))
    )
    (net (code "62") (name "Net-(Q5-B)") (class "Default")
      (node (ref "Q5") (pin "1") (pinfunction "B_1") (pintype "passive"))
      (node (ref "R8") (pin "2") (pinfunction "2_2") (pintype "passive"))
    )
    (net (code "63") (name "Net-(Q5-E)") (class "Default")
      (node (ref "Q5") (pin "2") (pinfunction "E_2") (pintype "passive"))
      (node (ref "R13") (pin "2") (pinfunction "2_2") (pintype "passive"))
      (node (ref "R14") (pin "2") (pinfunction "2_2") (pintype "passive"))
    )
    (net (code "64") (name "Net-(Q6-B)") (class "Default")
      (node (ref "Q6") (pin "1") (pinfunction "B_1") (pintype "passive"))
      (node (ref "R10") (pin "2") (pinfunction "2_2") (pintype "passive"))
      (node (ref "R9") (pin "2") (pinfunction "2_2") (pintype "passive"))
    )
    (net (code "65") (name "Net-(Q6-E)") (class "Default")
      (node (ref "Q6") (pin "2") (pinfunction "E_2") (pintype "passive"))
      (node (ref "R15") (pin "2") (pinfunction "2_2") (pintype "passive"))
      (node (ref "R16") (pin "2") (pinfunction "2_2") (pintype "passive"))
      (node (ref "R20") (pin "2") (pinfunction "2_2") (pintype "passive"))
    )
    (net (code "66") (name "Net-(Q7-B)") (class "Default")
      (node (ref "Q7") (pin "1") (pinfunction "B_1") (pintype "passive"))
      (node (ref "R29") (pin "2") (pinfunction "2_2") (pintype "passive"))
      (node (ref "R30") (pin "2") (pinfunction "2_2") (pintype "passive"))
    )
    (net (code "67") (name "Net-(Q7-E)") (class "Default")
      (node (ref "Q7") (pin "2") (pinfunction "E_2") (pintype "passive"))
      (node (ref "R31") (pin "2") (pinfunction "2_2") (pintype "passive"))
      (node (ref "R32") (pin "2") (pinfunction "2_2") (pintype "passive"))
      (node (ref "R33") (pin "2") (pinfunction "2_2") (pintype "passive"))
    )
    (net (code "68") (name "Net-(Q8-B)") (class "Default")
      (node (ref "Q8") (pin "1") (pinfunction "B_1") (pintype "passive"))
      (node (ref "R24") (pin "2") (pinfunction "2_2") (pintype "passive"))
      (node (ref "R25") (pin "2") (pinfunction "2_2") (pintype "passive"))
    )
    (net (code "69") (name "Net-(Q8-E)") (class "Default")
      (node (ref "Q8") (pin "2") (pinfunction "E_2") (pintype "passive"))
      (node (ref "R26") (pin "2") (pinfunction "2_2") (pintype "passive"))
      (node (ref "R27") (pin "2") (pinfunction "2_2") (pintype "passive"))
      (node (ref "R28") (pin "2") (pinfunction "2_2") (pintype "passive"))
    )
    (net (code "70") (name "Net-(R18-Pad2)") (class "Default")
      (node (ref "R18") (pin "2") (pinfunction "2_2") (pintype "passive"))
      (node (ref "R22") (pin "2") (pinfunction "2_2") (pintype "passive"))
    )
    (net (code "71") (name "Net-(R51-Pad2)") (class "Default")
      (node (ref "R51") (pin "2") (pinfunction "2_2") (pintype "passive"))
      (node (ref "SJ2") (pin "2") (pinfunction "2_2") (pintype "passive"))
    )
    (net (code "72") (name "Net-(T2-B)") (class "Default")
      (node (ref "C2") (pin "2") (pinfunction "2_2") (pintype "passive"))
      (node (ref "R18") (pin "1") (pinfunction "1_1") (pintype "passive"))
      (node (ref "R19") (pin "2") (pinfunction "2_2") (pintype "passive"))
      (node (ref "T2") (pin "1") (pinfunction "B_1") (pintype "passive"))
    )
    (net (code "73") (name "Net-(U$1-A0)") (class "Default")
      (node (ref "U$1") (pin "P20") (pinfunction "A0_P20") (pintype "bidirectional"))
      (node (ref "U1") (pin "P77") (pinfunction "IO_L20P_3_P77") (pintype "bidirectional"))
    )
    (net (code "74") (name "Net-(U$1-A1)") (class "Default")
      (node (ref "U$1") (pin "P19") (pinfunction "A1_P19") (pintype "bidirectional"))
      (node (ref "U1") (pin "P76") (pinfunction "IO_P76") (pintype "bidirectional"))
    )
    (net (code "75") (name "Net-(U$1-A2)") (class "Default")
      (node (ref "U$1") (pin "P18") (pinfunction "A2_P18") (pintype "bidirectional"))
      (node (ref "U1") (pin "P74") (pinfunction "IO_L01N_3VRP_3_P74") (pintype "bidirectional"))
    )
    (net (code "76") (name "Net-(U$1-A3)") (class "Default")
      (node (ref "U$1") (pin "P17") (pinfunction "A3_P17") (pintype "bidirectional"))
      (node (ref "U1") (pin "P73") (pinfunction "IO_L01P_3VRN_3_P73") (pintype "bidirectional"))
    )
    (net (code "77") (name "Net-(U$1-A4)") (class "Default")
      (node (ref "U$1") (pin "P16") (pinfunction "A4_P16") (pintype "bidirectional"))
      (node (ref "U1") (pin "P108") (pinfunction "IO_L01N_2VRP_2_P108") (pintype "bidirectional"))
    )
    (net (code "78") (name "Net-(U$1-A5)") (class "Default")
      (node (ref "U$1") (pin "P15") (pinfunction "A5_P15") (pintype "bidirectional"))
      (node (ref "U1") (pin "P107") (pinfunction "IO_L01P_2VRN_2_P107") (pintype "bidirectional"))
    )
    (net (code "79") (name "Net-(U$1-A6)") (class "Default")
      (node (ref "U$1") (pin "P14") (pinfunction "A6_P14") (pintype "bidirectional"))
      (node (ref "U1") (pin "P105") (pinfunction "IO_L20N_2_P105") (pintype "bidirectional"))
    )
    (net (code "80") (name "Net-(U$1-A7)") (class "Default")
      (node (ref "U$1") (pin "P13") (pinfunction "A7_P13") (pintype "bidirectional"))
      (node (ref "U1") (pin "P104") (pinfunction "IO_L20P_2_P104") (pintype "bidirectional"))
    )
    (net (code "81") (name "Net-(U$1-A8)") (class "Default")
      (node (ref "U$1") (pin "P3") (pinfunction "A8_P3") (pintype "bidirectional"))
      (node (ref "U1") (pin "P93") (pinfunction "IO_L40N_2_P93") (pintype "bidirectional"))
    )
    (net (code "82") (name "Net-(U$1-A9)") (class "Default")
      (node (ref "U$1") (pin "P2") (pinfunction "A9_P2") (pintype "bidirectional"))
      (node (ref "U1") (pin "P92") (pinfunction "IO_L40P_2VREF_2_P92") (pintype "bidirectional"))
    )
    (net (code "83") (name "Net-(U$1-A10)") (class "Default")
      (node (ref "U$1") (pin "P31") (pinfunction "A10_P31") (pintype "bidirectional"))
      (node (ref "U1") (pin "P87") (pinfunction "IO_L24N_3_P87") (pintype "bidirectional"))
    )
    (net (code "84") (name "Net-(U$1-A11)") (class "Default")
      (node (ref "U$1") (pin "P1") (pinfunction "A11_P1") (pintype "bidirectional"))
      (node (ref "U1") (pin "P90") (pinfunction "IO_L40N_3VREF_3_P90") (pintype "bidirectional"))
    )
    (net (code "85") (name "Net-(U$1-A12)") (class "Default")
      (node (ref "U$1") (pin "P12") (pinfunction "A12_P12") (pintype "bidirectional"))
      (node (ref "U1") (pin "P103") (pinfunction "IO_L21N_2_P103") (pintype "bidirectional"))
    )
    (net (code "86") (name "Net-(U$1-A13)") (class "Default")
      (node (ref "U$1") (pin "P4") (pinfunction "A13_P4") (pintype "bidirectional"))
      (node (ref "U1") (pin "P95") (pinfunction "IO_L24P_2_P95") (pintype "bidirectional"))
    )
    (net (code "87") (name "Net-(U$1-A14)") (class "Default")
      (node (ref "U$1") (pin "P11") (pinfunction "A14_P11") (pintype "bidirectional"))
      (node (ref "U1") (pin "P102") (pinfunction "IO_L21P_2_P102") (pintype "bidirectional"))
    )
    (net (code "88") (name "Net-(U$1-A15)") (class "Default")
      (node (ref "U$1") (pin "P7") (pinfunction "A15_P7") (pintype "bidirectional"))
      (node (ref "U1") (pin "P98") (pinfunction "IO_L23N_2VREF_2_P98") (pintype "bidirectional"))
    )
    (net (code "89") (name "Net-(U$1-A16)") (class "Default")
      (node (ref "U$1") (pin "P10") (pinfunction "A16_P10") (pintype "bidirectional"))
      (node (ref "U1") (pin "P100") (pinfunction "IO_L22N_2_P100") (pintype "bidirectional"))
    )
    (net (code "90") (name "Net-(U$1-A17)") (class "Default")
      (node (ref "U$1") (pin "P6") (pinfunction "A17_P6") (pintype "bidirectional"))
      (node (ref "U1") (pin "P97") (pinfunction "IO_L23P_2_P97") (pintype "bidirectional"))
    )
    (net (code "91") (name "Net-(U$1-A18)") (class "Default")
      (node (ref "U$1") (pin "P9") (pinfunction "A18_P9") (pintype "bidirectional"))
      (node (ref "U1") (pin "P99") (pinfunction "IO_L22P_2_P99") (pintype "bidirectional"))
    )
    (net (code "92") (name "Net-(U$1-DQ0)") (class "Default")
      (node (ref "U$1") (pin "P21") (pinfunction "DQ0_P21") (pintype "bidirectional"))
      (node (ref "U1") (pin "P78") (pinfunction "IO_L20N_3_P78") (pintype "bidirectional"))
    )
    (net (code "93") (name "Net-(U$1-DQ1)") (class "Default")
      (node (ref "U$1") (pin "P22") (pinfunction "DQ1_P22") (pintype "bidirectional"))
      (node (ref "U1") (pin "P79") (pinfunction "IO_L21P_3_P79") (pintype "bidirectional"))
    )
    (net (code "94") (name "Net-(U$1-DQ2)") (class "Default")
      (node (ref "U$1") (pin "P23") (pinfunction "DQ2_P23") (pintype "bidirectional"))
      (node (ref "U1") (pin "P80") (pinfunction "IO_L21N_3_P80") (pintype "bidirectional"))
    )
    (net (code "95") (name "Net-(U$1-DQ3)") (class "Default")
      (node (ref "U$1") (pin "P25") (pinfunction "DQ3_P25") (pintype "bidirectional"))
      (node (ref "U1") (pin "P82") (pinfunction "IO_L22P_3_P82") (pintype "bidirectional"))
    )
    (net (code "96") (name "Net-(U$1-DQ4)") (class "Default")
      (node (ref "U$1") (pin "P26") (pinfunction "DQ4_P26") (pintype "bidirectional"))
      (node (ref "U1") (pin "P83") (pinfunction "IO_L22N_3_P83") (pintype "bidirectional"))
    )
    (net (code "97") (name "Net-(U$1-DQ5)") (class "Default")
      (node (ref "U$1") (pin "P27") (pinfunction "DQ5_P27") (pintype "bidirectional"))
      (node (ref "U1") (pin "P84") (pinfunction "IO_L23P_3VREF_3_P84") (pintype "bidirectional"))
    )
    (net (code "98") (name "Net-(U$1-DQ6)") (class "Default")
      (node (ref "U$1") (pin "P28") (pinfunction "DQ6_P28") (pintype "bidirectional"))
      (node (ref "U1") (pin "P85") (pinfunction "IO_L23N_3_P85") (pintype "bidirectional"))
    )
    (net (code "99") (name "Net-(U$1-DQ7)") (class "Default")
      (node (ref "U$1") (pin "P29") (pinfunction "DQ7_P29") (pintype "bidirectional"))
      (node (ref "U1") (pin "P86") (pinfunction "IO_L24P_3_P86") (pintype "bidirectional"))
    )
    (net (code "100") (name "Net-(U$1-OE)") (class "Default")
      (node (ref "U$1") (pin "P32") (pinfunction "OE_P32") (pintype "bidirectional"))
      (node (ref "U1") (pin "P89") (pinfunction "IO_L40P_3_P89") (pintype "bidirectional"))
    )
    (net (code "101") (name "Net-(U$1-WE)") (class "Default")
      (node (ref "U$1") (pin "P5") (pinfunction "WE_P5") (pintype "bidirectional"))
      (node (ref "U1") (pin "P96") (pinfunction "IO_L24N_2_P96") (pintype "bidirectional"))
    )
    (net (code "102") (name "Net-(U1I-IO_L32P_5GCLK2)") (class "Default")
      (node (ref "U$2") (pin "OUT") (pinfunction "OUT_OUT") (pintype "output"))
      (node (ref "U1") (pin "P52") (pinfunction "IO_L32P_5GCLK2_P52") (pintype "bidirectional"))
    )
    (net (code "103") (name "Net-(U1N-TCK)") (class "Default")
      (node (ref "R2") (pin "1") (pinfunction "1_1") (pintype "passive"))
      (node (ref "U1") (pin "P110") (pinfunction "TCK_P110") (pintype "bidirectional"))
    )
    (net (code "104") (name "Net-(U1N-TDI)") (class "Default")
      (node (ref "R1") (pin "1") (pinfunction "1_1") (pintype "passive"))
      (node (ref "U1") (pin "P144") (pinfunction "TDI_P144") (pintype "bidirectional"))
    )
    (net (code "105") (name "Net-(U1N-TMS)") (class "Default")
      (node (ref "R3") (pin "1") (pinfunction "1_1") (pintype "passive"))
      (node (ref "U1") (pin "P111") (pinfunction "TMS_P111") (pintype "bidirectional"))
    )
    (net (code "106") (name "Net-(X4A-F)") (class "Default")
      (node (ref "R40") (pin "2") (pinfunction "2_2") (pintype "passive"))
      (node (ref "X4") (pin "1") (pinfunction "F_1") (pintype "passive"))
    )
    (net (code "107") (name "Net-(X4B-F)") (class "Default")
      (node (ref "R41") (pin "2") (pinfunction "2_2") (pintype "passive"))
      (node (ref "X4") (pin "2") (pinfunction "F_2") (pintype "passive"))
    )
    (net (code "108") (name "Net-(X4C-F)") (class "Default")
      (node (ref "R42") (pin "2") (pinfunction "2_2") (pintype "passive"))
      (node (ref "X4") (pin "3") (pinfunction "F_3") (pintype "passive"))
    )
    (net (code "109") (name "Net-(X4D-F)") (class "Default")
      (node (ref "R43") (pin "2") (pinfunction "2_2") (pintype "passive"))
      (node (ref "X4") (pin "4") (pinfunction "F_4") (pintype "passive"))
    )
    (net (code "110") (name "Net-(X4F-F)") (class "Default")
      (node (ref "R44") (pin "2") (pinfunction "2_2") (pintype "passive"))
      (node (ref "X4") (pin "6") (pinfunction "F_6") (pintype "passive"))
    )
    (net (code "111") (name "Net-(X4G-F)") (class "Default")
      (node (ref "R45") (pin "2") (pinfunction "2_2") (pintype "passive"))
      (node (ref "X4") (pin "7") (pinfunction "F_7") (pintype "passive"))
    )
    (net (code "112") (name "Net-(X5A-F)") (class "Default")
      (node (ref "R46") (pin "1") (pinfunction "1_1") (pintype "passive"))
      (node (ref "X5") (pin "1") (pinfunction "F_1") (pintype "passive"))
    )
    (net (code "113") (name "Net-(X5B-F)") (class "Default")
      (node (ref "R39") (pin "1") (pinfunction "1_1") (pintype "passive"))
      (node (ref "X5") (pin "2") (pinfunction "F_2") (pintype "passive"))
    )
    (net (code "114") (name "Net-(X5C-F)") (class "Default")
      (node (ref "R38") (pin "1") (pinfunction "1_1") (pintype "passive"))
      (node (ref "X5") (pin "3") (pinfunction "F_3") (pintype "passive"))
    )
    (net (code "115") (name "Net-(X5D-F)") (class "Default")
      (node (ref "R37") (pin "1") (pinfunction "1_1") (pintype "passive"))
      (node (ref "X5") (pin "4") (pinfunction "F_4") (pintype "passive"))
    )
    (net (code "116") (name "Net-(X5F-F)") (class "Default")
      (node (ref "R36") (pin "1") (pinfunction "1_1") (pintype "passive"))
      (node (ref "X5") (pin "6") (pinfunction "F_6") (pintype "passive"))
    )
    (net (code "117") (name "Net-(X5G-F)") (class "Default")
      (node (ref "R35") (pin "1") (pinfunction "1_1") (pintype "passive"))
      (node (ref "X5") (pin "7") (pinfunction "F_7") (pintype "passive"))
    )
    (net (code "118") (name "unconnected-(IC1-NC.1-Pad2)") (class "Default")
      (node (ref "IC1") (pin "2") (pinfunction "NC.1_2") (pintype "bidirectional"))
    )
    (net (code "119") (name "unconnected-(IC1-NC.2-Pad9)") (class "Default")
      (node (ref "IC1") (pin "9") (pinfunction "NC.2_9") (pintype "bidirectional"))
    )
    (net (code "120") (name "unconnected-(IC1-NC.3-Pad12)") (class "Default")
      (node (ref "IC1") (pin "12") (pinfunction "NC.3_12") (pintype "bidirectional"))
    )
    (net (code "121") (name "unconnected-(IC1-NC.4-Pad14)") (class "Default")
      (node (ref "IC1") (pin "14") (pinfunction "NC.4_14") (pintype "bidirectional"))
    )
    (net (code "122") (name "unconnected-(IC1-NC.5-Pad15)") (class "Default")
      (node (ref "IC1") (pin "15") (pinfunction "NC.5_15") (pintype "bidirectional"))
    )
    (net (code "123") (name "unconnected-(IC1-NC.6-Pad16)") (class "Default")
      (node (ref "IC1") (pin "16") (pinfunction "NC.6_16") (pintype "bidirectional"))
    )
    (net (code "124") (name "unconnected-(IC1-{slash}CEO-Pad13)") (class "Default")
      (node (ref "IC1") (pin "13") (pinfunction "/CEO_13") (pintype "bidirectional"))
    )
    (net (code "125") (name "unconnected-(REG1.2-VOUT2-Pad2)") (class "Default")
      (node (ref "REG1.2") (pin "2") (pinfunction "VOUT2_2") (pintype "bidirectional"))
    )
    (net (code "126") (name "unconnected-(U$2-TRI-PadENA)") (class "Default")
      (node (ref "U$2") (pin "ENA") (pinfunction "TRI_ENA") (pintype "input"))
    )
    (net (code "127") (name "unconnected-(U$3-AREF-Pad42)") (class "Default")
      (node (ref "U$3") (pin "42") (pinfunction "AREF_42") (pintype "bidirectional"))
    )
    (net (code "128") (name "unconnected-(U$3-AVCC-Pad24)") (class "Default")
      (node (ref "U$3") (pin "24") (pinfunction "AVCC_24") (pintype "bidirectional"))
    )
    (net (code "129") (name "unconnected-(U$3-AVCC1-Pad44)") (class "Default")
      (node (ref "U$3") (pin "44") (pinfunction "AVCC1_44") (pintype "bidirectional"))
    )
    (net (code "130") (name "unconnected-(U$3-D+-Pad4)") (class "Default")
      (node (ref "U$3") (pin "4") (pinfunction "D+_4") (pintype "bidirectional"))
    )
    (net (code "131") (name "unconnected-(U$3-D--Pad3)") (class "Default")
      (node (ref "U$3") (pin "3") (pinfunction "D-_3") (pintype "bidirectional"))
    )
    (net (code "132") (name "unconnected-(U$3-GND-Pad15)") (class "Default")
      (node (ref "U$3") (pin "15") (pinfunction "GND_15") (pintype "bidirectional"))
    )
    (net (code "133") (name "unconnected-(U$3-GND1-Pad23)") (class "Default")
      (node (ref "U$3") (pin "23") (pinfunction "GND1_23") (pintype "bidirectional"))
    )
    (net (code "134") (name "unconnected-(U$3-GND2-Pad35)") (class "Default")
      (node (ref "U$3") (pin "35") (pinfunction "GND2_35") (pintype "bidirectional"))
    )
    (net (code "135") (name "unconnected-(U$3-GND3-Pad43)") (class "Default")
      (node (ref "U$3") (pin "43") (pinfunction "GND3_43") (pintype "bidirectional"))
    )
    (net (code "136") (name "unconnected-(U$3-PB4(ADC11)-Pad28)") (class "Default")
      (node (ref "U$3") (pin "28") (pinfunction "PB4(ADC11)_28") (pintype "bidirectional"))
    )
    (net (code "137") (name "unconnected-(U$3-PB5(OC1A{slash}ADC12{slash}~{OC4B})-Pad29)") (class "Default")
      (node (ref "U$3") (pin "29") (pinfunction "PB5(OC1A/ADC12/~{OC4B})_29") (pintype "bidirectional"))
    )
    (net (code "138") (name "unconnected-(U$3-PB6(OC1B{slash}OC4B{slash}ADC13)-Pad30)") (class "Default")
      (node (ref "U$3") (pin "30") (pinfunction "PB6(OC1B/OC4B/ADC13)_30") (pintype "bidirectional"))
    )
    (net (code "139") (name "unconnected-(U$3-PB7(OC0A{slash}OC1C{slash}RTS)-Pad12)") (class "Default")
      (node (ref "U$3") (pin "12") (pinfunction "PB7(OC0A/OC1C/RTS)_12") (pintype "bidirectional"))
    )
    (net (code "140") (name "unconnected-(U$3-PC6(OC3A{slash}~{OC4A})-Pad31)") (class "Default")
      (node (ref "U$3") (pin "31") (pinfunction "PC6(OC3A/~{OC4A})_31") (pintype "bidirectional"))
    )
    (net (code "141") (name "unconnected-(U$3-PC7(ICP3{slash}CLK0{slash}OC4A)-Pad32)") (class "Default")
      (node (ref "U$3") (pin "32") (pinfunction "PC7(ICP3/CLK0/OC4A)_32") (pintype "bidirectional"))
    )
    (net (code "142") (name "unconnected-(U$3-PD0(INT0{slash}OC0B{slash}SCL)-Pad18)") (class "Default")
      (node (ref "U$3") (pin "18") (pinfunction "PD0(INT0/OC0B/SCL)_18") (pintype "bidirectional"))
    )
    (net (code "143") (name "unconnected-(U$3-PD1(INT1{slash}SDA)-Pad19)") (class "Default")
      (node (ref "U$3") (pin "19") (pinfunction "PD1(INT1/SDA)_19") (pintype "bidirectional"))
    )
    (net (code "144") (name "unconnected-(U$3-PD2(INT2{slash}RXD1)-Pad20)") (class "Default")
      (node (ref "U$3") (pin "20") (pinfunction "PD2(INT2/RXD1)_20") (pintype "bidirectional"))
    )
    (net (code "145") (name "unconnected-(U$3-PD3(INT3{slash}TXD1)-Pad21)") (class "Default")
      (node (ref "U$3") (pin "21") (pinfunction "PD3(INT3/TXD1)_21") (pintype "bidirectional"))
    )
    (net (code "146") (name "unconnected-(U$3-PD4(ICP1{slash}ADC8)-Pad25)") (class "Default")
      (node (ref "U$3") (pin "25") (pinfunction "PD4(ICP1/ADC8)_25") (pintype "bidirectional"))
    )
    (net (code "147") (name "unconnected-(U$3-PD5(XCK{slash}CTS)-Pad22)") (class "Default")
      (node (ref "U$3") (pin "22") (pinfunction "PD5(XCK/CTS)_22") (pintype "bidirectional"))
    )
    (net (code "148") (name "unconnected-(U$3-PD6(T1{slash}ADC9{slash}~{OC4D})-Pad26)") (class "Default")
      (node (ref "U$3") (pin "26") (pinfunction "PD6(T1/ADC9/~{OC4D})_26") (pintype "bidirectional"))
    )
    (net (code "149") (name "unconnected-(U$3-PD7(OC4D{slash}ADC10{slash}T0)-Pad27)") (class "Default")
      (node (ref "U$3") (pin "27") (pinfunction "PD7(OC4D/ADC10/T0)_27") (pintype "bidirectional"))
    )
    (net (code "150") (name "unconnected-(U$3-PE2(~{HWB})-Pad33)") (class "Default")
      (node (ref "U$3") (pin "33") (pinfunction "PE2(~{HWB})_33") (pintype "bidirectional"))
    )
    (net (code "151") (name "unconnected-(U$3-PE6(INT.6{slash}AIN0)-Pad1)") (class "Default")
      (node (ref "U$3") (pin "1") (pinfunction "PE6(INT.6/AIN0)_1") (pintype "bidirectional"))
    )
    (net (code "152") (name "unconnected-(U$3-PF0(ADC0)-Pad41)") (class "Default")
      (node (ref "U$3") (pin "41") (pinfunction "PF0(ADC0)_41") (pintype "bidirectional"))
    )
    (net (code "153") (name "unconnected-(U$3-PF1(ADC1)-Pad40)") (class "Default")
      (node (ref "U$3") (pin "40") (pinfunction "PF1(ADC1)_40") (pintype "bidirectional"))
    )
    (net (code "154") (name "unconnected-(U$3-UCAP-Pad6)") (class "Default")
      (node (ref "U$3") (pin "6") (pinfunction "UCAP_6") (pintype "bidirectional"))
    )
    (net (code "155") (name "unconnected-(U$3-UGND-Pad5)") (class "Default")
      (node (ref "U$3") (pin "5") (pinfunction "UGND_5") (pintype "bidirectional"))
    )
    (net (code "156") (name "unconnected-(U$3-UVCC-Pad2)") (class "Default")
      (node (ref "U$3") (pin "2") (pinfunction "UVCC_2") (pintype "bidirectional"))
    )
    (net (code "157") (name "unconnected-(U$3-VBUS-Pad7)") (class "Default")
      (node (ref "U$3") (pin "7") (pinfunction "VBUS_7") (pintype "bidirectional"))
    )
    (net (code "158") (name "unconnected-(U$3-VCC-Pad14)") (class "Default")
      (node (ref "U$3") (pin "14") (pinfunction "VCC_14") (pintype "bidirectional"))
    )
    (net (code "159") (name "unconnected-(U$3-VCC1-Pad34)") (class "Default")
      (node (ref "U$3") (pin "34") (pinfunction "VCC1_34") (pintype "bidirectional"))
    )
    (net (code "160") (name "unconnected-(U$3-XTAL1-Pad17)") (class "Default")
      (node (ref "U$3") (pin "17") (pinfunction "XTAL1_17") (pintype "bidirectional"))
    )
    (net (code "161") (name "unconnected-(U$3-XTAL2-Pad16)") (class "Default")
      (node (ref "U$3") (pin "16") (pinfunction "XTAL2_16") (pintype "bidirectional"))
    )
    (net (code "162") (name "unconnected-(U$3-{slash}RESET-Pad13)") (class "Default")
      (node (ref "U$3") (pin "13") (pinfunction "/RESET_13") (pintype "bidirectional"))
    )
    (net (code "163") (name "unconnected-(U1A-IO_L27P_0-PadP135)") (class "Default")
      (node (ref "U1") (pin "P135") (pinfunction "IO_L27P_0_P135") (pintype "bidirectional"))
    )
    (net (code "164") (name "unconnected-(U1A-IO_L30N_0-PadP132)") (class "Default")
      (node (ref "U1") (pin "P132") (pinfunction "IO_L30N_0_P132") (pintype "bidirectional"))
    )
    (net (code "165") (name "unconnected-(U1A-IO_L30P_0-PadP131)") (class "Default")
      (node (ref "U1") (pin "P131") (pinfunction "IO_L30P_0_P131") (pintype "bidirectional"))
    )
    (net (code "166") (name "unconnected-(U1A-IO_L31N_0-PadP130)") (class "Default")
      (node (ref "U1") (pin "P130") (pinfunction "IO_L31N_0_P130") (pintype "bidirectional"))
    )
    (net (code "167") (name "unconnected-(U1A-IO_L31P_0VREF_0-PadP129)") (class "Default")
      (node (ref "U1") (pin "P129") (pinfunction "IO_L31P_0VREF_0_P129") (pintype "bidirectional"))
    )
    (net (code "168") (name "unconnected-(U1A-IO_L32N_0GCLK7-PadP128)") (class "Default")
      (node (ref "U1") (pin "P128") (pinfunction "IO_L32N_0GCLK7_P128") (pintype "bidirectional"))
    )
    (net (code "169") (name "unconnected-(U1A-IO_L32P_0GCLK6-PadP127)") (class "Default")
      (node (ref "U1") (pin "P127") (pinfunction "IO_L32P_0GCLK6_P127") (pintype "bidirectional"))
    )
    (net (code "170") (name "unconnected-(U1C-IO-PadP116)") (class "Default")
      (node (ref "U1") (pin "P116") (pinfunction "IO_P116") (pintype "bidirectional"))
    )
    (net (code "171") (name "unconnected-(U1C-IO_L01N_1VRP_1-PadP113)") (class "Default")
      (node (ref "U1") (pin "P113") (pinfunction "IO_L01N_1VRP_1_P113") (pintype "bidirectional"))
    )
    (net (code "172") (name "unconnected-(U1C-IO_L01P_1VRN_1-PadP112)") (class "Default")
      (node (ref "U1") (pin "P112") (pinfunction "IO_L01P_1VRN_1_P112") (pintype "bidirectional"))
    )
    (net (code "173") (name "unconnected-(U1C-IO_L28N_1-PadP119)") (class "Default")
      (node (ref "U1") (pin "P119") (pinfunction "IO_L28N_1_P119") (pintype "bidirectional"))
    )
    (net (code "174") (name "unconnected-(U1C-IO_L28P_1-PadP118)") (class "Default")
      (node (ref "U1") (pin "P118") (pinfunction "IO_L28P_1_P118") (pintype "bidirectional"))
    )
    (net (code "175") (name "unconnected-(U1C-IO_L31N_1VREF_1-PadP123)") (class "Default")
      (node (ref "U1") (pin "P123") (pinfunction "IO_L31N_1VREF_1_P123") (pintype "bidirectional"))
    )
    (net (code "176") (name "unconnected-(U1C-IO_L31P_1-PadP122)") (class "Default")
      (node (ref "U1") (pin "P122") (pinfunction "IO_L31P_1_P122") (pintype "bidirectional"))
    )
    (net (code "177") (name "unconnected-(U1C-IO_L32N_1GCLK5-PadP125)") (class "Default")
      (node (ref "U1") (pin "P125") (pinfunction "IO_L32N_1GCLK5_P125") (pintype "bidirectional"))
    )
    (net (code "178") (name "unconnected-(U1C-IO_L32P_1GCLK4-PadP124)") (class "Default")
      (node (ref "U1") (pin "P124") (pinfunction "IO_L32P_1GCLK4_P124") (pintype "bidirectional"))
    )
    (net (code "179") (name "unconnected-(U1G-IOVREF_4-PadP70)") (class "Default")
      (node (ref "U1") (pin "P70") (pinfunction "IOVREF_4_P70") (pintype "bidirectional"))
    )
    (net (code "180") (name "unconnected-(U1G-IO_L01N_4VRP_4-PadP69)") (class "Default")
      (node (ref "U1") (pin "P69") (pinfunction "IO_L01N_4VRP_4_P69") (pintype "bidirectional"))
    )
    (net (code "181") (name "unconnected-(U1G-IO_L01P_4VRN_4-PadP68)") (class "Default")
      (node (ref "U1") (pin "P68") (pinfunction "IO_L01P_4VRN_4_P68") (pintype "bidirectional"))
    )
    (net (code "182") (name "unconnected-(U1G-IO_L27P_4D1-PadP63)") (class "Default")
      (node (ref "U1") (pin "P63") (pinfunction "IO_L27P_4D1_P63") (pintype "bidirectional"))
    )
    (net (code "183") (name "unconnected-(U1G-IO_L30N_4D2-PadP60)") (class "Default")
      (node (ref "U1") (pin "P60") (pinfunction "IO_L30N_4D2_P60") (pintype "bidirectional"))
    )
    (net (code "184") (name "unconnected-(U1G-IO_L30P_4D3-PadP59)") (class "Default")
      (node (ref "U1") (pin "P59") (pinfunction "IO_L30P_4D3_P59") (pintype "bidirectional"))
    )
    (net (code "185") (name "unconnected-(U1G-IO_L31P_4DOUTBUSY-PadP57)") (class "Default")
      (node (ref "U1") (pin "P57") (pinfunction "IO_L31P_4DOUTBUSY_P57") (pintype "bidirectional"))
    )
    (net (code "186") (name "unconnected-(U1G-IO_L32N_4GCLK1-PadP56)") (class "Default")
      (node (ref "U1") (pin "P56") (pinfunction "IO_L32N_4GCLK1_P56") (pintype "bidirectional"))
    )
    (net (code "187") (name "unconnected-(U1G-IO_L32P_4GCLK0-PadP55)") (class "Default")
      (node (ref "U1") (pin "P55") (pinfunction "IO_L32P_4GCLK0_P55") (pintype "bidirectional"))
    )
    (net (code "188") (name "unconnected-(U1I-IO_L32N_5GCLK3-PadP53)") (class "Default")
      (node (ref "U1") (pin "P53") (pinfunction "IO_L32N_5GCLK3_P53") (pintype "bidirectional"))
    )
    (net (code "189") (name "unconnected-(U1J-IO_L01N_6VRP_6-PadP36)") (class "Default")
      (node (ref "U1") (pin "P36") (pinfunction "IO_L01N_6VRP_6_P36") (pintype "bidirectional"))
    )
    (net (code "190") (name "unconnected-(U1J-IO_L01P_6VRN_6-PadP35)") (class "Default")
      (node (ref "U1") (pin "P35") (pinfunction "IO_L01P_6VRN_6_P35") (pintype "bidirectional"))
    )
    (net (code "191") (name "unconnected-(U1J-IO_L20N_6-PadP33)") (class "Default")
      (node (ref "U1") (pin "P33") (pinfunction "IO_L20N_6_P33") (pintype "bidirectional"))
    )
    (net (code "192") (name "unconnected-(U1J-IO_L20P_6-PadP32)") (class "Default")
      (node (ref "U1") (pin "P32") (pinfunction "IO_L20P_6_P32") (pintype "bidirectional"))
    )
    (net (code "193") (name "unconnected-(U1J-IO_L21N_6-PadP31)") (class "Default")
      (node (ref "U1") (pin "P31") (pinfunction "IO_L21N_6_P31") (pintype "bidirectional"))
    )
    (net (code "194") (name "unconnected-(U1J-IO_L21P_6-PadP30)") (class "Default")
      (node (ref "U1") (pin "P30") (pinfunction "IO_L21P_6_P30") (pintype "bidirectional"))
    )
    (net (code "195") (name "unconnected-(U1J-IO_L22N_6-PadP28)") (class "Default")
      (node (ref "U1") (pin "P28") (pinfunction "IO_L22N_6_P28") (pintype "bidirectional"))
    )
    (net (code "196") (name "unconnected-(U1J-IO_L22P_6-PadP27)") (class "Default")
      (node (ref "U1") (pin "P27") (pinfunction "IO_L22P_6_P27") (pintype "bidirectional"))
    )
    (net (code "197") (name "unconnected-(U1J-IO_L23N_6-PadP26)") (class "Default")
      (node (ref "U1") (pin "P26") (pinfunction "IO_L23N_6_P26") (pintype "bidirectional"))
    )
    (net (code "198") (name "unconnected-(U1J-IO_L23P_6-PadP25)") (class "Default")
      (node (ref "U1") (pin "P25") (pinfunction "IO_L23P_6_P25") (pintype "bidirectional"))
    )
    (net (code "199") (name "unconnected-(U1J-IO_L24N_6VREF_6-PadP24)") (class "Default")
      (node (ref "U1") (pin "P24") (pinfunction "IO_L24N_6VREF_6_P24") (pintype "bidirectional"))
    )
    (net (code "200") (name "unconnected-(U1J-IO_L24P_6-PadP23)") (class "Default")
      (node (ref "U1") (pin "P23") (pinfunction "IO_L24P_6_P23") (pintype "bidirectional"))
    )
    (net (code "201") (name "unconnected-(U1J-IO_L40N_6-PadP21)") (class "Default")
      (node (ref "U1") (pin "P21") (pinfunction "IO_L40N_6_P21") (pintype "bidirectional"))
    )
    (net (code "202") (name "unconnected-(U1J-IO_L40P_6VREF_6-PadP20)") (class "Default")
      (node (ref "U1") (pin "P20") (pinfunction "IO_L40P_6VREF_6_P20") (pintype "bidirectional"))
    )
    (net (code "203") (name "unconnected-(U1L-IOVREF_7-PadP4)") (class "Default")
      (node (ref "U1") (pin "P4") (pinfunction "IOVREF_7_P4") (pintype "bidirectional"))
    )
    (net (code "204") (name "unconnected-(U1L-IO_L01N_7VRP_7-PadP2)") (class "Default")
      (node (ref "U1") (pin "P2") (pinfunction "IO_L01N_7VRP_7_P2") (pintype "bidirectional"))
    )
    (net (code "205") (name "unconnected-(U1L-IO_L01P_7VRN_7-PadP1)") (class "Default")
      (node (ref "U1") (pin "P1") (pinfunction "IO_L01P_7VRN_7_P1") (pintype "bidirectional"))
    )
    (net (code "206") (name "unconnected-(U1L-IO_L20N_7-PadP6)") (class "Default")
      (node (ref "U1") (pin "P6") (pinfunction "IO_L20N_7_P6") (pintype "bidirectional"))
    )
    (net (code "207") (name "unconnected-(U1L-IO_L20P_7-PadP5)") (class "Default")
      (node (ref "U1") (pin "P5") (pinfunction "IO_L20P_7_P5") (pintype "bidirectional"))
    )
    (net (code "208") (name "unconnected-(U1L-IO_L21N_7-PadP8)") (class "Default")
      (node (ref "U1") (pin "P8") (pinfunction "IO_L21N_7_P8") (pintype "bidirectional"))
    )
    (net (code "209") (name "unconnected-(U1L-IO_L21P_7-PadP7)") (class "Default")
      (node (ref "U1") (pin "P7") (pinfunction "IO_L21P_7_P7") (pintype "bidirectional"))
    )
    (net (code "210") (name "unconnected-(U1L-IO_L22N_7-PadP11)") (class "Default")
      (node (ref "U1") (pin "P11") (pinfunction "IO_L22N_7_P11") (pintype "bidirectional"))
    )
    (net (code "211") (name "unconnected-(U1L-IO_L22P_7-PadP10)") (class "Default")
      (node (ref "U1") (pin "P10") (pinfunction "IO_L22P_7_P10") (pintype "bidirectional"))
    )
    (net (code "212") (name "unconnected-(U1L-IO_L23N_7-PadP13)") (class "Default")
      (node (ref "U1") (pin "P13") (pinfunction "IO_L23N_7_P13") (pintype "bidirectional"))
    )
    (net (code "213") (name "unconnected-(U1L-IO_L23P_7-PadP12)") (class "Default")
      (node (ref "U1") (pin "P12") (pinfunction "IO_L23P_7_P12") (pintype "bidirectional"))
    )
    (net (code "214") (name "unconnected-(U1L-IO_L24N_7-PadP15)") (class "Default")
      (node (ref "U1") (pin "P15") (pinfunction "IO_L24N_7_P15") (pintype "bidirectional"))
    )
    (net (code "215") (name "unconnected-(U1L-IO_L24P_7-PadP14)") (class "Default")
      (node (ref "U1") (pin "P14") (pinfunction "IO_L24P_7_P14") (pintype "bidirectional"))
    )
    (net (code "216") (name "unconnected-(U1L-IO_L40N_7VREF_7-PadP18)") (class "Default")
      (node (ref "U1") (pin "P18") (pinfunction "IO_L40N_7VREF_7_P18") (pintype "bidirectional"))
    )
    (net (code "217") (name "unconnected-(U1L-IO_L40P_7-PadP17)") (class "Default")
      (node (ref "U1") (pin "P17") (pinfunction "IO_L40P_7_P17") (pintype "bidirectional"))
    )
    (net (code "218") (name "unconnected-(U1N-HSWAP_EN-PadP142)") (class "Default")
      (node (ref "U1") (pin "P142") (pinfunction "HSWAP_EN_P142") (pintype "bidirectional"))
    )
    (net (code "219") (name "unconnected-(X1-3-Pad2)") (class "Default")
      (node (ref "X1") (pin "2") (pinfunction "3_2") (pintype "passive"))
    )
    (net (code "220") (name "unconnected-(X2-Pad10)") (class "Default")
      (node (ref "X2") (pin "10") (pinfunction "10_10") (pintype "passive"))
    )
    (net (code "221") (name "unconnected-(X2-Pad12)") (class "Default")
      (node (ref "X2") (pin "12") (pinfunction "12_12") (pintype "passive"))
    )
    (net (code "222") (name "unconnected-(X3-Pad2)") (class "Default")
      (node (ref "X3") (pin "2") (pinfunction "2_2") (pintype "passive"))
    )
    (net (code "223") (name "unconnected-(X3-Pad8)") (class "Default")
      (node (ref "X3") (pin "8") (pinfunction "8_8") (pintype "passive"))
    )
    (net (code "224") (name "unconnected-(X4-PadG2)") (class "Default")
      (node (ref "X4") (pin "G2") (pinfunction "G2_G2") (pintype "passive"))
    )
    (net (code "225") (name "unconnected-(X5-PadG2)") (class "Default")
      (node (ref "X5") (pin "G2") (pinfunction "G2_G2") (pintype "passive"))
    )
  )
)
